# Main_Circuit.net
KiCad netlist of a schematic drawn in Altium Designer
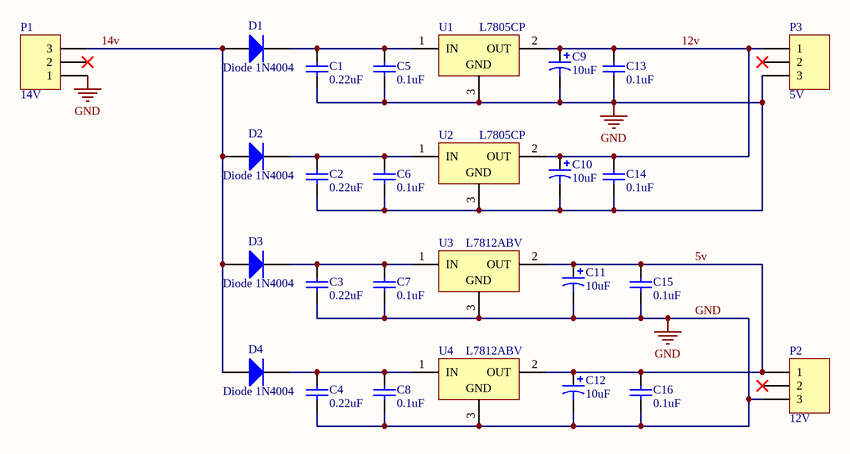
[diagram p0: Main_Circuit.SchDoc]

(export (version "E")
  (design (tool "Eeschema 10.0.6"))
  (components
    (comp (ref "C1")
      (value "0.22uF")
      (footprint "RAD-0.3")
      (description "Capacitor")
      (fields (field (name "Comment") "Cap") (field (name "PUBLISHER") "Altium Limited"))
      (libsource (lib "Miscellaneous Devices") (part "Cap"))
    )
    (comp (ref "C2")
      (value "0.22uF")
      (footprint "RAD-0.3")
      (description "Capacitor")
      (fields (field (name "Comment") "Cap") (field (name "PUBLISHER") "Altium Limited"))
      (libsource (lib "Miscellaneous Devices") (part "Cap"))
    )
    (comp (ref "C3")
      (value "0.22uF")
      (footprint "RAD-0.3")
      (description "Capacitor")
      (fields (field (name "Comment") "Cap") (field (name "PUBLISHER") "Altium Limited"))
      (libsource (lib "Miscellaneous Devices") (part "Cap"))
    )
    (comp (ref "C4")
      (value "0.22uF")
      (footprint "RAD-0.3")
      (description "Capacitor")
      (fields (field (name "Comment") "Cap") (field (name "PUBLISHER") "Altium Limited"))
      (libsource (lib "Miscellaneous Devices") (part "Cap"))
    )
    (comp (ref "C5")
      (value "0.1uF")
      (footprint "RAD-0.3")
      (description "Capacitor")
      (fields (field (name "Comment") "Cap") (field (name "PUBLISHER") "Altium Limited"))
      (libsource (lib "Miscellaneous Devices") (part "Cap"))
    )
    (comp (ref "C6")
      (value "0.1uF")
      (footprint "RAD-0.3")
      (description "Capacitor")
      (fields (field (name "Comment") "Cap") (field (name "PUBLISHER") "Altium Limited"))
      (libsource (lib "Miscellaneous Devices") (part "Cap"))
    )
    (comp (ref "C7")
      (value "0.1uF")
      (footprint "RAD-0.3")
      (description "Capacitor")
      (fields (field (name "Comment") "Cap") (field (name "PUBLISHER") "Altium Limited"))
      (libsource (lib "Miscellaneous Devices") (part "Cap"))
    )
    (comp (ref "C8")
      (value "0.1uF")
      (footprint "RAD-0.3")
      (description "Capacitor")
      (fields (field (name "Comment") "Cap") (field (name "PUBLISHER") "Altium Limited"))
      (libsource (lib "Miscellaneous Devices") (part "Cap"))
    )
    (comp (ref "C9")
      (value "10uF")
      (footprint "RB7.6-15")
      (description "Polarized Capacitor (Radial)")
      (fields (field (name "Comment") "Cap Pol1") (field (name "PUBLISHER") "Altium Limited"))
      (libsource (lib "Miscellaneous Devices") (part "Cap Pol1"))
    )
    (comp (ref "C10")
      (value "10uF")
      (footprint "RB7.6-15")
      (description "Polarized Capacitor (Radial)")
      (fields (field (name "Comment") "Cap Pol1") (field (name "PUBLISHER") "Altium Limited"))
      (libsource (lib "Miscellaneous Devices") (part "Cap Pol1"))
    )
    (comp (ref "C11")
      (value "10uF")
      (footprint "RB7.6-15")
      (description "Polarized Capacitor (Radial)")
      (fields (field (name "Comment") "Cap Pol1") (field (name "PUBLISHER") "Altium Limited"))
      (libsource (lib "Miscellaneous Devices") (part "Cap Pol1"))
    )
    (comp (ref "C12")
      (value "10uF")
      (footprint "RB7.6-15")
      (description "Polarized Capacitor (Radial)")
      (fields (field (name "Comment") "Cap Pol1") (field (name "PUBLISHER") "Altium Limited"))
      (libsource (lib "Miscellaneous Devices") (part "Cap Pol1"))
    )
    (comp (ref "C13")
      (value "0.1uF")
      (footprint "RAD-0.3")
      (description "Capacitor")
      (fields (field (name "Comment") "Cap") (field (name "PUBLISHER") "Altium Limited"))
      (libsource (lib "Miscellaneous Devices") (part "Cap"))
    )
    (comp (ref "C14")
      (value "0.1uF")
      (footprint "RAD-0.3")
      (description "Capacitor")
      (fields (field (name "Comment") "Cap") (field (name "PUBLISHER") "Altium Limited"))
      (libsource (lib "Miscellaneous Devices") (part "Cap"))
    )
    (comp (ref "C15")
      (value "0.1uF")
      (footprint "RAD-0.3")
      (description "Capacitor")
      (fields (field (name "Comment") "Cap") (field (name "PUBLISHER") "Altium Limited"))
      (libsource (lib "Miscellaneous Devices") (part "Cap"))
    )
    (comp (ref "C16")
      (value "0.1uF")
      (footprint "RAD-0.3")
      (description "Capacitor")
      (fields (field (name "Comment") "Cap") (field (name "PUBLISHER") "Altium Limited"))
      (libsource (lib "Miscellaneous Devices") (part "Cap"))
    )
    (comp (ref "D1")
      (value "Diode 1N4004")
      (footprint "DO-41")
      (description "1 Amp General Purpose Rectifier")
      (fields (field (name "PUBLISHER") "Altium Limited"))
      (libsource (lib "Miscellaneous Devices") (part "Diode 1N4004"))
    )
    (comp (ref "D2")
      (value "Diode 1N4004")
      (footprint "DO-41")
      (description "1 Amp General Purpose Rectifier")
      (fields (field (name "PUBLISHER") "Altium Limited"))
      (libsource (lib "Miscellaneous Devices") (part "Diode 1N4004"))
    )
    (comp (ref "D3")
      (value "Diode 1N4004")
      (footprint "DO-41")
      (description "1 Amp General Purpose Rectifier")
      (fields (field (name "PUBLISHER") "Altium Limited"))
      (libsource (lib "Miscellaneous Devices") (part "Diode 1N4004"))
    )
    (comp (ref "D4")
      (value "Diode 1N4004")
      (footprint "DO-41")
      (description "1 Amp General Purpose Rectifier")
      (fields (field (name "PUBLISHER") "Altium Limited"))
      (libsource (lib "Miscellaneous Devices") (part "Diode 1N4004"))
    )
    (comp (ref "P1")
      (value "14V")
      (footprint "HDR1X3")
      (description "Header, 3-Pin")
      (fields (field (name "PUBLISHER") "Altium Limited"))
      (libsource (lib "") (part "Header 3_1"))
    )
    (comp (ref "P2")
      (value "12V")
      (footprint "HDR1X3")
      (description "Header, 3-Pin")
      (fields (field (name "PUBLISHER") "Altium Limited"))
      (libsource (lib "Miscellaneous Connectors") (part "Header 3"))
    )
    (comp (ref "P3")
      (value "5V")
      (footprint "HDR1X3")
      (description "Header, 3-Pin")
      (fields (field (name "PUBLISHER") "Altium Limited"))
      (libsource (lib "Miscellaneous Connectors") (part "Header 3"))
    )
    (comp (ref "U1")
      (value "L7805CP")
      (footprint "ISOWATT220AB")
      (description "Positive Voltage Regulator")
      (fields (field (name "PUBLISHER") "Altium Limited"))
      (libsource (lib "ST Power Mgt Voltage Regulator") (part "L7805CP"))
    )
    (comp (ref "U2")
      (value "L7805CP")
      (footprint "ISOWATT220AB")
      (description "Positive Voltage Regulator")
      (fields (field (name "PUBLISHER") "Altium Limited"))
      (libsource (lib "ST Power Mgt Voltage Regulator") (part "L7805CP"))
    )
    (comp (ref "U3")
      (value "L7812ABV")
      (footprint "TO220ABN")
      (description "Precision 1A Regulator")
      (fields (field (name "PUBLISHER") "Altium Limited"))
      (libsource (lib "ST Power Mgt Voltage Regulator") (part "L7812ABV"))
    )
    (comp (ref "U4")
      (value "L7812ABV")
      (footprint "TO220ABN")
      (description "Precision 1A Regulator")
      (fields (field (name "PUBLISHER") "Altium Limited"))
      (libsource (lib "ST Power Mgt Voltage Regulator") (part "L7812ABV"))
    )
  )
  (nets
    (net (code "1") (name "/5v") (class "Default")
      (node (ref "C11") (pin "1") (pinfunction "1_1") (pintype "passive"))
      (node (ref "C12") (pin "1") (pinfunction "1_1") (pintype "passive"))
      (node (ref "C15") (pin "2") (pinfunction "2_2") (pintype "passive"))
      (node (ref "C16") (pin "2") (pinfunction "2_2") (pintype "passive"))
      (node (ref "P2") (pin "1") (pinfunction "1_1") (pintype "passive"))
      (node (ref "U3") (pin "2") (pinfunction "OUT_2") (pintype "power_in"))
      (node (ref "U4") (pin "2") (pinfunction "OUT_2") (pintype "power_in"))
    )
    (net (code "2") (name "/12v") (class "Default")
      (node (ref "C10") (pin "1") (pinfunction "1_1") (pintype "passive"))
      (node (ref "C13") (pin "2") (pinfunction "2_2") (pintype "passive"))
      (node (ref "C14") (pin "2") (pinfunction "2_2") (pintype "passive"))
      (node (ref "C9") (pin "1") (pinfunction "1_1") (pintype "passive"))
      (node (ref "P3") (pin "1") (pinfunction "1_1") (pintype "passive"))
      (node (ref "U1") (pin "2") (pinfunction "OUT_2") (pintype "power_in"))
      (node (ref "U2") (pin "2") (pinfunction "OUT_2") (pintype "power_in"))
    )
    (net (code "3") (name "/14v") (class "Default")
      (node (ref "D1") (pin "1") (pinfunction "A_1") (pintype "passive"))
      (node (ref "D2") (pin "1") (pinfunction "A_1") (pintype "passive"))
      (node (ref "D3") (pin "1") (pinfunction "A_1") (pintype "passive"))
      (node (ref "D4") (pin "1") (pinfunction "A_1") (pintype "passive"))
      (node (ref "P1") (pin "3") (pinfunction "3_3") (pintype "passive"))
    )
    (net (code "4") (name "GND") (class "Default")
      (node (ref "C1") (pin "1") (pinfunction "1_1") (pintype "passive"))
      (node (ref "C10") (pin "2") (pinfunction "2_2") (pintype "passive"))
      (node (ref "C11") (pin "2") (pinfunction "2_2") (pintype "passive"))
      (node (ref "C12") (pin "2") (pinfunction "2_2") (pintype "passive"))
      (node (ref "C13") (pin "1") (pinfunction "1_1") (pintype "passive"))
      (node (ref "C14") (pin "1") (pinfunction "1_1") (pintype "passive"))
      (node (ref "C15") (pin "1") (pinfunction "1_1") (pintype "passive"))
      (node (ref "C16") (pin "1") (pinfunction "1_1") (pintype "passive"))
      (node (ref "C2") (pin "1") (pinfunction "1_1") (pintype "passive"))
      (node (ref "C3") (pin "1") (pinfunction "1_1") (pintype "passive"))
      (node (ref "C4") (pin "1") (pinfunction "1_1") (pintype "passive"))
      (node (ref "C5") (pin "1") (pinfunction "1_1") (pintype "passive"))
      (node (ref "C6") (pin "1") (pinfunction "1_1") (pintype "passive"))
      (node (ref "C7") (pin "1") (pinfunction "1_1") (pintype "passive"))
      (node (ref "C8") (pin "1") (pinfunction "1_1") (pintype "passive"))
      (node (ref "C9") (pin "2") (pinfunction "2_2") (pintype "passive"))
      (node (ref "P1") (pin "1") (pinfunction "1_1") (pintype "passive"))
      (node (ref "P2") (pin "3") (pinfunction "3_3") (pintype "passive"))
      (node (ref "P3") (pin "3") (pinfunction "3_3") (pintype "passive"))
      (node (ref "U1") (pin "3") (pinfunction "GND_3") (pintype "power_in"))
      (node (ref "U2") (pin "3") (pinfunction "GND_3") (pintype "power_in"))
      (node (ref "U3") (pin "3") (pinfunction "GND_3") (pintype "power_in"))
      (node (ref "U4") (pin "3") (pinfunction "GND_3") (pintype "power_in"))
    )
    (net (code "5") (name "Net-(D1-K)") (class "Default")
      (node (ref "C1") (pin "2") (pinfunction "2_2") (pintype "passive"))
      (node (ref "C5") (pin "2") (pinfunction "2_2") (pintype "passive"))
      (node (ref "D1") (pin "2") (pinfunction "K_2") (pintype "passive"))
      (node (ref "U1") (pin "1") (pinfunction "IN_1") (pintype "power_in"))
    )
    (net (code "6") (name "Net-(D2-K)") (class "Default")
      (node (ref "C2") (pin "2") (pinfunction "2_2") (pintype "passive"))
      (node (ref "C6") (pin "2") (pinfunction "2_2") (pintype "passive"))
      (node (ref "D2") (pin "2") (pinfunction "K_2") (pintype "passive"))
      (node (ref "U2") (pin "1") (pinfunction "IN_1") (pintype "power_in"))
    )
    (net (code "7") (name "Net-(D3-K)") (class "Default")
      (node (ref "C3") (pin "2") (pinfunction "2_2") (pintype "passive"))
      (node (ref "C7") (pin "2") (pinfunction "2_2") (pintype "passive"))
      (node (ref "D3") (pin "2") (pinfunction "K_2") (pintype "passive"))
      (node (ref "U3") (pin "1") (pinfunction "IN_1") (pintype "power_in"))
    )
    (net (code "8") (name "Net-(D4-K)") (class "Default")
      (node (ref "C4") (pin "2") (pinfunction "2_2") (pintype "passive"))
      (node (ref "C8") (pin "2") (pinfunction "2_2") (pintype "passive"))
      (node (ref "D4") (pin "2") (pinfunction "K_2") (pintype "passive"))
      (node (ref "U4") (pin "1") (pinfunction "IN_1") (pintype "power_in"))
    )
    (net (code "9") (name "unconnected-(P1-Pad2)") (class "Default")
      (node (ref "P1") (pin "2") (pinfunction "2_2") (pintype "passive+no_connect"))
    )
    (net (code "10") (name "unconnected-(P2-Pad2)") (class "Default")
      (node (ref "P2") (pin "2") (pinfunction "2_2") (pintype "passive+no_connect"))
    )
    (net (code "11") (name "unconnected-(P3-Pad2)") (class "Default")
      (node (ref "P3") (pin "2") (pinfunction "2_2") (pintype "passive+no_connect"))
    )
  )
)
